# PCB1M1A2.net
KiCad netlist of a schematic drawn in EAGLE
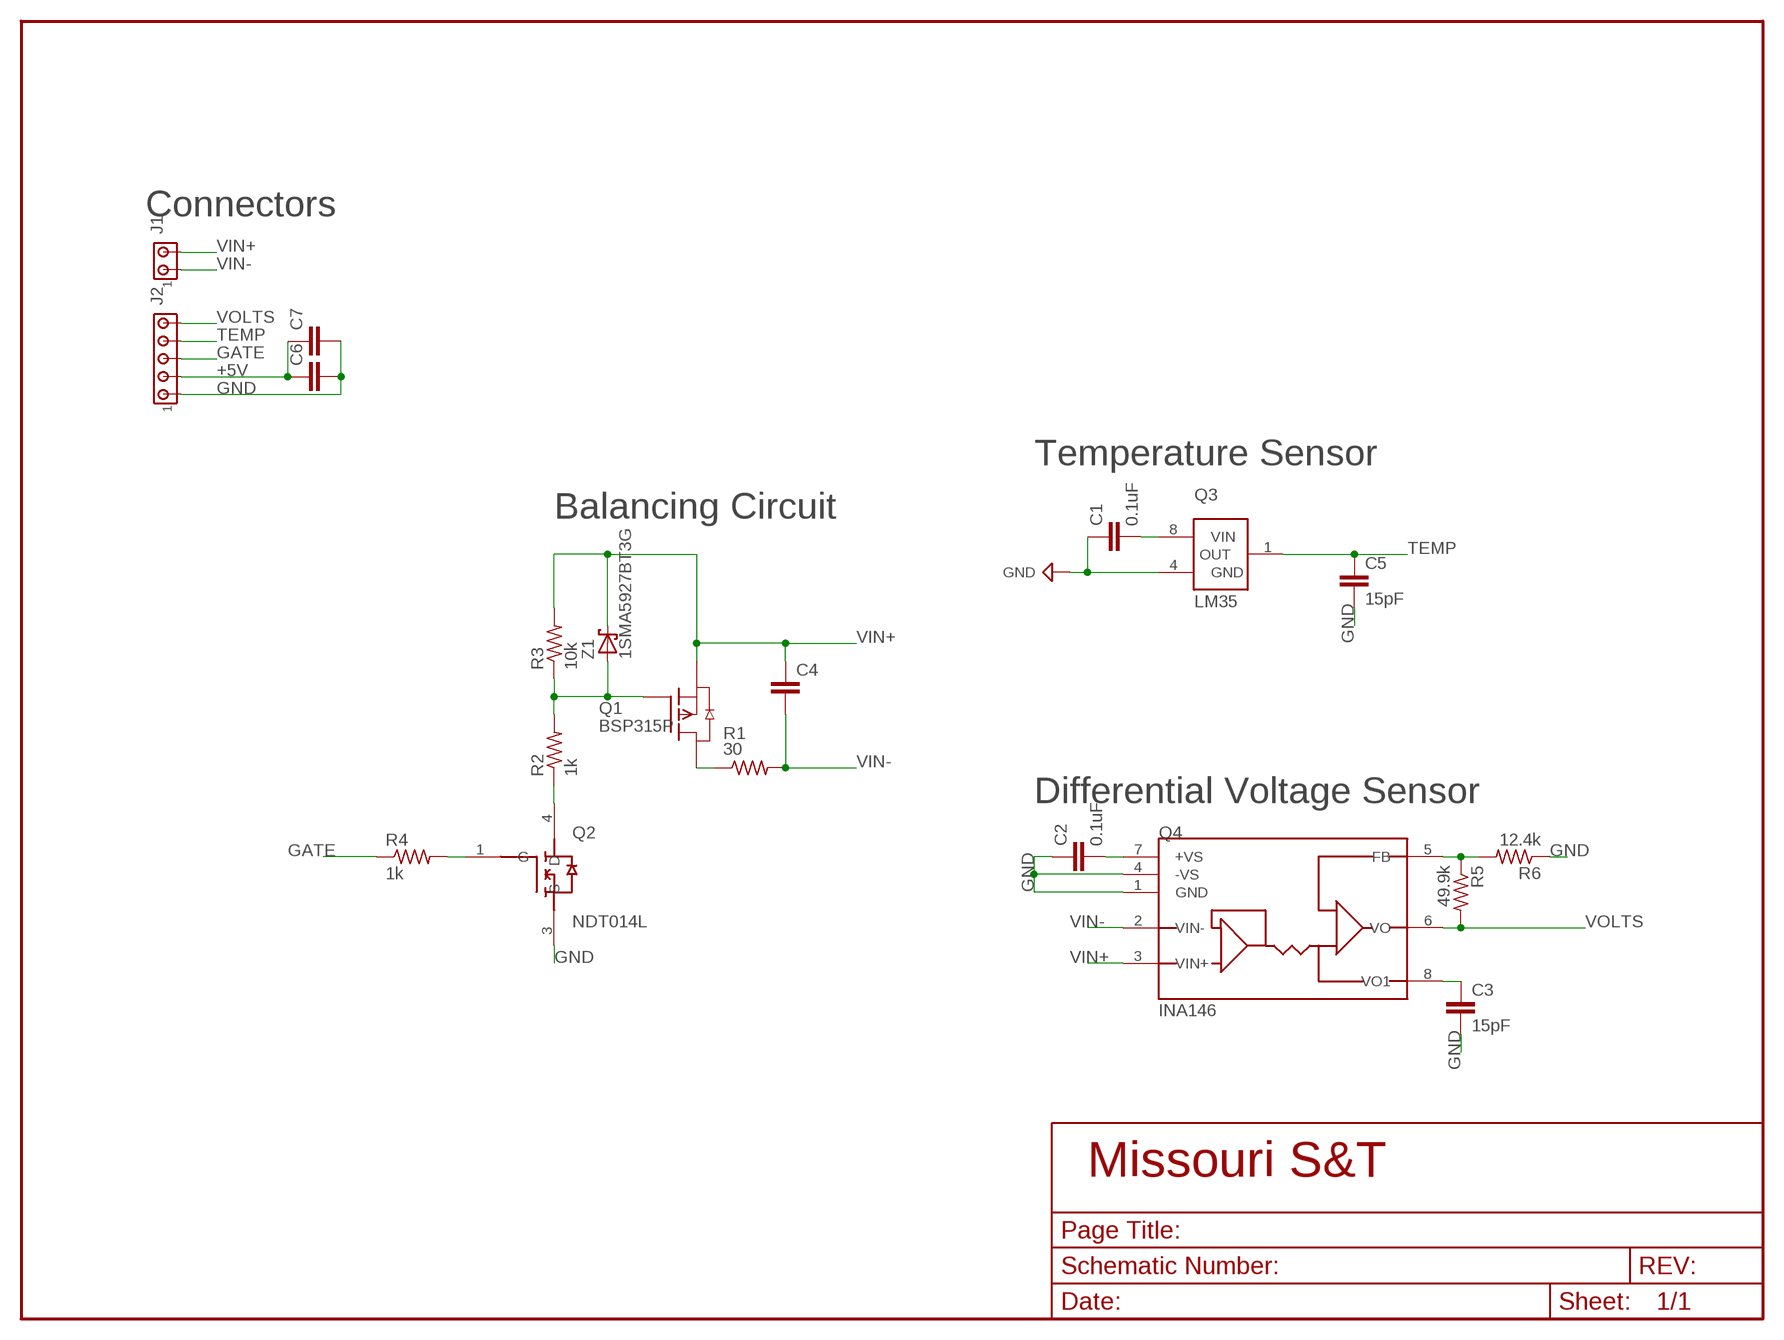
[diagram p0: schematic, sheet 1]

(export (version "E")
  (design (tool "Eeschema 10.0.6"))
  (components
    (comp (ref "C1")
      (value "0.1uF")
      (footprint "eagle-import:C_1206")
      (libsource (lib "eagle-import") (part "C_CAP_1206"))
    )
    (comp (ref "C2")
      (value "0.1uF")
      (footprint "eagle-import:C_1206")
      (libsource (lib "eagle-import") (part "C_CAP_1206"))
    )
    (comp (ref "C3")
      (value "15pF")
      (footprint "eagle-import:C_1206")
      (libsource (lib "eagle-import") (part "C_CAP_1206"))
    )
    (comp (ref "C4")
      (value "C_CAP_1206")
      (footprint "eagle-import:C_1206")
      (libsource (lib "eagle-import") (part "C_CAP_1206"))
    )
    (comp (ref "C5")
      (value "15pF")
      (footprint "eagle-import:C_1206")
      (libsource (lib "eagle-import") (part "C_CAP_1206"))
    )
    (comp (ref "C6")
      (value "C_CAP_1206")
      (footprint "eagle-import:C_1206")
      (libsource (lib "eagle-import") (part "C_CAP_1206"))
    )
    (comp (ref "C7")
      (value "C_CAP_1206")
      (footprint "eagle-import:C_1206")
      (libsource (lib "eagle-import") (part "C_CAP_1206"))
    )
    (comp (ref "J1")
      (value "J_MTA2P_100")
      (footprint "eagle-import:J_MTA100_2P")
      (libsource (lib "eagle-import") (part "J_MTA2P_100"))
    )
    (comp (ref "J2")
      (value "J_MTA5P_100")
      (footprint "eagle-import:J_MTA100_5P")
      (libsource (lib "eagle-import") (part "J_MTA5P_100"))
    )
    (comp (ref "Q1")
      (value "BSP315P")
      (footprint "eagle-import:SOT-223")
      (libsource (lib "eagle-import") (part "Q_BSP315P"))
    )
    (comp (ref "Q2")
      (value "NDT014L")
      (footprint "eagle-import:SOT-223")
      (libsource (lib "eagle-import") (part "Q_NDT014L"))
    )
    (comp (ref "Q3")
      (value "LM35")
      (footprint "eagle-import:SOIC8")
      (libsource (lib "eagle-import") (part "Q_LM35SOIC8"))
    )
    (comp (ref "Q4")
      (value "INA146")
      (footprint "eagle-import:SOIC8")
      (libsource (lib "eagle-import") (part "Q_INA146"))
    )
    (comp (ref "R1")
      (value "30")
      (footprint "eagle-import:R_2512")
      (libsource (lib "eagle-import") (part "R_2512"))
    )
    (comp (ref "R2")
      (value "1k")
      (footprint "eagle-import:R_1206")
      (libsource (lib "eagle-import") (part "R_RES_1206"))
    )
    (comp (ref "R3")
      (value "10k")
      (footprint "eagle-import:R_1206")
      (libsource (lib "eagle-import") (part "R_RES_1206"))
    )
    (comp (ref "R4")
      (value "1k")
      (footprint "eagle-import:R_1206")
      (libsource (lib "eagle-import") (part "R_RES_1206"))
    )
    (comp (ref "R5")
      (value "49.9k")
      (footprint "eagle-import:R_1206")
      (libsource (lib "eagle-import") (part "R_RES_1206"))
    )
    (comp (ref "R6")
      (value "12.4k")
      (footprint "eagle-import:R_1206")
      (libsource (lib "eagle-import") (part "R_RES_1206"))
    )
    (comp (ref "Z1")
      (value "1SMA5927BT3G")
      (footprint "eagle-import:D_DO214AC")
      (libsource (lib "eagle-import") (part "D_SSA34-E3/61T"))
    )
  )
  (nets
    (net (code "1") (name "/+5V") (class "Default")
      (node (ref "C1") (pin "2") (pinfunction "2_2") (pintype "passive"))
      (node (ref "C2") (pin "2") (pinfunction "2_2") (pintype "passive"))
      (node (ref "C6") (pin "1") (pinfunction "1_1") (pintype "passive"))
      (node (ref "C7") (pin "1") (pinfunction "1_1") (pintype "passive"))
      (node (ref "J2") (pin "2") (pinfunction "2_2") (pintype "passive"))
      (node (ref "Q3") (pin "8") (pinfunction "VIN_8") (pintype "bidirectional"))
      (node (ref "Q4") (pin "7") (pinfunction "+VS_7") (pintype "bidirectional"))
    )
    (net (code "2") (name "/GATE") (class "Default")
      (node (ref "J2") (pin "3") (pinfunction "3_3") (pintype "passive"))
      (node (ref "R4") (pin "1") (pinfunction "1_1") (pintype "passive"))
    )
    (net (code "3") (name "/TEMP") (class "Default")
      (node (ref "C5") (pin "1") (pinfunction "1_1") (pintype "passive"))
      (node (ref "J2") (pin "4") (pinfunction "4_4") (pintype "passive"))
      (node (ref "Q3") (pin "1") (pinfunction "OUT_1") (pintype "bidirectional"))
    )
    (net (code "4") (name "/VIN+") (class "Default")
      (node (ref "C4") (pin "1") (pinfunction "1_1") (pintype "passive"))
      (node (ref "J1") (pin "2") (pinfunction "2_2") (pintype "passive"))
      (node (ref "Q1") (pin "3") (pinfunction "S_3") (pintype "passive"))
      (node (ref "Q4") (pin "3") (pinfunction "VIN+_3") (pintype "bidirectional"))
      (node (ref "R3") (pin "2") (pinfunction "2_2") (pintype "passive"))
      (node (ref "Z1") (pin "C") (pinfunction "C_C") (pintype "passive"))
    )
    (net (code "5") (name "/VIN-") (class "Default")
      (node (ref "C4") (pin "2") (pinfunction "2_2") (pintype "passive"))
      (node (ref "J1") (pin "1") (pinfunction "1_1") (pintype "passive"))
      (node (ref "Q4") (pin "2") (pinfunction "VIN-_2") (pintype "bidirectional"))
      (node (ref "R1") (pin "P$2") (pinfunction "2_P$2") (pintype "passive"))
    )
    (net (code "6") (name "/VOLTS") (class "Default")
      (node (ref "J2") (pin "5") (pinfunction "5_5") (pintype "passive"))
      (node (ref "Q4") (pin "6") (pinfunction "VO_6") (pintype "bidirectional"))
      (node (ref "R5") (pin "2") (pinfunction "2_2") (pintype "passive"))
    )
    (net (code "7") (name "Net-(Q1-D)") (class "Default")
      (node (ref "Q1") (pin "2") (pinfunction "D_2") (pintype "passive"))
      (node (ref "R1") (pin "P$1") (pinfunction "1_P$1") (pintype "passive"))
    )
    (net (code "8") (name "Net-(Q1-G)") (class "Default")
      (node (ref "Q1") (pin "1") (pinfunction "G_1") (pintype "passive"))
      (node (ref "R2") (pin "2") (pinfunction "2_2") (pintype "passive"))
      (node (ref "R3") (pin "1") (pinfunction "1_1") (pintype "passive"))
      (node (ref "Z1") (pin "A") (pinfunction "A_A") (pintype "passive"))
    )
    (net (code "9") (name "Net-(Q2-D)") (class "Default")
      (node (ref "Q2") (pin "4") (pinfunction "D_4") (pintype "bidirectional"))
      (node (ref "R2") (pin "1") (pinfunction "1_1") (pintype "passive"))
    )
    (net (code "10") (name "Net-(Q2-G)") (class "Default")
      (node (ref "Q2") (pin "1") (pinfunction "G_1") (pintype "bidirectional"))
      (node (ref "R4") (pin "2") (pinfunction "2_2") (pintype "passive"))
    )
    (net (code "11") (name "Net-(Q4-FB)") (class "Default")
      (node (ref "Q4") (pin "5") (pinfunction "FB_5") (pintype "bidirectional"))
      (node (ref "R5") (pin "1") (pinfunction "1_1") (pintype "passive"))
      (node (ref "R6") (pin "2") (pinfunction "2_2") (pintype "passive"))
    )
    (net (code "12") (name "Net-(Q4-VO1)") (class "Default")
      (node (ref "C3") (pin "1") (pinfunction "1_1") (pintype "passive"))
      (node (ref "Q4") (pin "8") (pinfunction "VO1_8") (pintype "bidirectional"))
    )
    (net (code "13") (name "SUP_GND") (class "Default")
      (node (ref "C1") (pin "1") (pinfunction "1_1") (pintype "passive"))
      (node (ref "C2") (pin "1") (pinfunction "1_1") (pintype "passive"))
      (node (ref "C3") (pin "2") (pinfunction "2_2") (pintype "passive"))
      (node (ref "C5") (pin "2") (pinfunction "2_2") (pintype "passive"))
      (node (ref "C6") (pin "2") (pinfunction "2_2") (pintype "passive"))
      (node (ref "C7") (pin "2") (pinfunction "2_2") (pintype "passive"))
      (node (ref "J2") (pin "1") (pinfunction "1_1") (pintype "passive"))
      (node (ref "Q2") (pin "3") (pinfunction "S_3") (pintype "bidirectional"))
      (node (ref "Q3") (pin "4") (pinfunction "GND_4") (pintype "bidirectional"))
      (node (ref "Q4") (pin "1") (pinfunction "GND_1") (pintype "bidirectional"))
      (node (ref "Q4") (pin "4") (pinfunction "-VS_4") (pintype "bidirectional"))
      (node (ref "R6") (pin "1") (pinfunction "1_1") (pintype "passive"))
    )
  )
)
